# Pinduino-Nano-WPC-adaptor-panalized.net
KiCad netlist of a schematic drawn in EAGLE
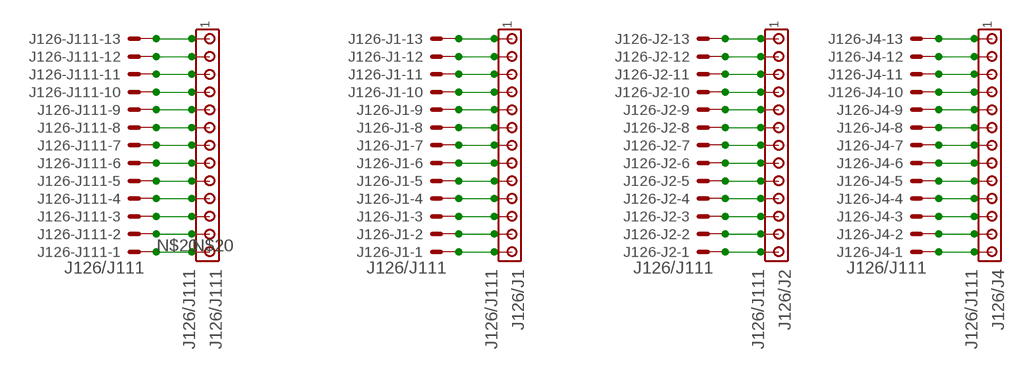
[diagram p0: schematic, sheet 1]

(export (version "E")
  (design (tool "Eeschema 10.0.6"))
  (components
    (comp (ref "J126-J1")
      (value "J126/J111")
      (footprint "eagle-import:KK-156-13")
      (libsource (lib "eagle-import") (part "KK-156-13"))
    )
    (comp (ref "J126-J2")
      (value "J126/J111")
      (footprint "eagle-import:KK-156-13")
      (libsource (lib "eagle-import") (part "KK-156-13"))
    )
    (comp (ref "J126-J4")
      (value "J126/J111")
      (footprint "eagle-import:KK-156-13")
      (libsource (lib "eagle-import") (part "KK-156-13"))
    )
    (comp (ref "J126-J111")
      (value "J126/J111")
      (footprint "eagle-import:KK-156-13")
      (libsource (lib "eagle-import") (part "KK-156-13"))
    )
    (comp (ref "J126/J1")
      (value "J126/J111")
      (footprint "eagle-import:1X13MTA")
      (libsource (lib "eagle-import") (part "MTA13-156"))
    )
    (comp (ref "J126/J2")
      (value "J126/J111")
      (footprint "eagle-import:1X13MTA")
      (libsource (lib "eagle-import") (part "MTA13-156"))
    )
    (comp (ref "J126/J4")
      (value "J126/J111")
      (footprint "eagle-import:1X13MTA")
      (libsource (lib "eagle-import") (part "MTA13-156"))
    )
    (comp (ref "J126/J111")
      (value "J126/J111")
      (footprint "eagle-import:1X13MTA")
      (libsource (lib "eagle-import") (part "MTA13-156"))
    )
  )
  (nets
    (net (code "1") (name "/N$20") (class "Default")
      (node (ref "J126-J111") (pin "2") (pinfunction "S_2") (pintype "passive"))
      (node (ref "J126/J111") (pin "12") (pinfunction "12_12") (pintype "passive"))
    )
    (net (code "2") (name "Net-(J126-J1A-S)") (class "Default")
      (node (ref "J126-J1") (pin "1") (pinfunction "S_1") (pintype "passive"))
      (node (ref "J126/J1") (pin "13") (pinfunction "13_13") (pintype "passive"))
    )
    (net (code "3") (name "Net-(J126-J1B-S)") (class "Default")
      (node (ref "J126-J1") (pin "10") (pinfunction "S_10") (pintype "passive"))
      (node (ref "J126/J1") (pin "4") (pinfunction "4_4") (pintype "passive"))
    )
    (net (code "4") (name "Net-(J126-J1C-S)") (class "Default")
      (node (ref "J126-J1") (pin "11") (pinfunction "S_11") (pintype "passive"))
      (node (ref "J126/J1") (pin "3") (pinfunction "3_3") (pintype "passive"))
    )
    (net (code "5") (name "Net-(J126-J1D-S)") (class "Default")
      (node (ref "J126-J1") (pin "12") (pinfunction "S_12") (pintype "passive"))
      (node (ref "J126/J1") (pin "2") (pinfunction "2_2") (pintype "passive"))
    )
    (net (code "6") (name "Net-(J126-J1E-S)") (class "Default")
      (node (ref "J126-J1") (pin "13") (pinfunction "S_13") (pintype "passive"))
      (node (ref "J126/J1") (pin "1") (pinfunction "1_1") (pintype "passive"))
    )
    (net (code "7") (name "Net-(J126-J1F-S)") (class "Default")
      (node (ref "J126-J1") (pin "2") (pinfunction "S_2") (pintype "passive"))
      (node (ref "J126/J1") (pin "12") (pinfunction "12_12") (pintype "passive"))
    )
    (net (code "8") (name "Net-(J126-J1G-S)") (class "Default")
      (node (ref "J126-J1") (pin "3") (pinfunction "S_3") (pintype "passive"))
      (node (ref "J126/J1") (pin "11") (pinfunction "11_11") (pintype "passive"))
    )
    (net (code "9") (name "Net-(J126-J1H-S)") (class "Default")
      (node (ref "J126-J1") (pin "4") (pinfunction "S_4") (pintype "passive"))
      (node (ref "J126/J1") (pin "10") (pinfunction "10_10") (pintype "passive"))
    )
    (net (code "10") (name "Net-(J126-J1I-S)") (class "Default")
      (node (ref "J126-J1") (pin "5") (pinfunction "S_5") (pintype "passive"))
      (node (ref "J126/J1") (pin "9") (pinfunction "9_9") (pintype "passive"))
    )
    (net (code "11") (name "Net-(J126-J1J-S)") (class "Default")
      (node (ref "J126-J1") (pin "6") (pinfunction "S_6") (pintype "passive"))
      (node (ref "J126/J1") (pin "8") (pinfunction "8_8") (pintype "passive"))
    )
    (net (code "12") (name "Net-(J126-J1K-S)") (class "Default")
      (node (ref "J126-J1") (pin "7") (pinfunction "S_7") (pintype "passive"))
      (node (ref "J126/J1") (pin "7") (pinfunction "7_7") (pintype "passive"))
    )
    (net (code "13") (name "Net-(J126-J1L-S)") (class "Default")
      (node (ref "J126-J1") (pin "8") (pinfunction "S_8") (pintype "passive"))
      (node (ref "J126/J1") (pin "6") (pinfunction "6_6") (pintype "passive"))
    )
    (net (code "14") (name "Net-(J126-J1M-S)") (class "Default")
      (node (ref "J126-J1") (pin "9") (pinfunction "S_9") (pintype "passive"))
      (node (ref "J126/J1") (pin "5") (pinfunction "5_5") (pintype "passive"))
    )
    (net (code "15") (name "Net-(J126-J2A-S)") (class "Default")
      (node (ref "J126-J2") (pin "1") (pinfunction "S_1") (pintype "passive"))
      (node (ref "J126/J2") (pin "13") (pinfunction "13_13") (pintype "passive"))
    )
    (net (code "16") (name "Net-(J126-J2B-S)") (class "Default")
      (node (ref "J126-J2") (pin "10") (pinfunction "S_10") (pintype "passive"))
      (node (ref "J126/J2") (pin "4") (pinfunction "4_4") (pintype "passive"))
    )
    (net (code "17") (name "Net-(J126-J2C-S)") (class "Default")
      (node (ref "J126-J2") (pin "11") (pinfunction "S_11") (pintype "passive"))
      (node (ref "J126/J2") (pin "3") (pinfunction "3_3") (pintype "passive"))
    )
    (net (code "18") (name "Net-(J126-J2D-S)") (class "Default")
      (node (ref "J126-J2") (pin "12") (pinfunction "S_12") (pintype "passive"))
      (node (ref "J126/J2") (pin "2") (pinfunction "2_2") (pintype "passive"))
    )
    (net (code "19") (name "Net-(J126-J2E-S)") (class "Default")
      (node (ref "J126-J2") (pin "13") (pinfunction "S_13") (pintype "passive"))
      (node (ref "J126/J2") (pin "1") (pinfunction "1_1") (pintype "passive"))
    )
    (net (code "20") (name "Net-(J126-J2F-S)") (class "Default")
      (node (ref "J126-J2") (pin "2") (pinfunction "S_2") (pintype "passive"))
      (node (ref "J126/J2") (pin "12") (pinfunction "12_12") (pintype "passive"))
    )
    (net (code "21") (name "Net-(J126-J2G-S)") (class "Default")
      (node (ref "J126-J2") (pin "3") (pinfunction "S_3") (pintype "passive"))
      (node (ref "J126/J2") (pin "11") (pinfunction "11_11") (pintype "passive"))
    )
    (net (code "22") (name "Net-(J126-J2H-S)") (class "Default")
      (node (ref "J126-J2") (pin "4") (pinfunction "S_4") (pintype "passive"))
      (node (ref "J126/J2") (pin "10") (pinfunction "10_10") (pintype "passive"))
    )
    (net (code "23") (name "Net-(J126-J2I-S)") (class "Default")
      (node (ref "J126-J2") (pin "5") (pinfunction "S_5") (pintype "passive"))
      (node (ref "J126/J2") (pin "9") (pinfunction "9_9") (pintype "passive"))
    )
    (net (code "24") (name "Net-(J126-J2J-S)") (class "Default")
      (node (ref "J126-J2") (pin "6") (pinfunction "S_6") (pintype "passive"))
      (node (ref "J126/J2") (pin "8") (pinfunction "8_8") (pintype "passive"))
    )
    (net (code "25") (name "Net-(J126-J2K-S)") (class "Default")
      (node (ref "J126-J2") (pin "7") (pinfunction "S_7") (pintype "passive"))
      (node (ref "J126/J2") (pin "7") (pinfunction "7_7") (pintype "passive"))
    )
    (net (code "26") (name "Net-(J126-J2L-S)") (class "Default")
      (node (ref "J126-J2") (pin "8") (pinfunction "S_8") (pintype "passive"))
      (node (ref "J126/J2") (pin "6") (pinfunction "6_6") (pintype "passive"))
    )
    (net (code "27") (name "Net-(J126-J2M-S)") (class "Default")
      (node (ref "J126-J2") (pin "9") (pinfunction "S_9") (pintype "passive"))
      (node (ref "J126/J2") (pin "5") (pinfunction "5_5") (pintype "passive"))
    )
    (net (code "28") (name "Net-(J126-J4A-S)") (class "Default")
      (node (ref "J126-J4") (pin "1") (pinfunction "S_1") (pintype "passive"))
      (node (ref "J126/J4") (pin "13") (pinfunction "13_13") (pintype "passive"))
    )
    (net (code "29") (name "Net-(J126-J4B-S)") (class "Default")
      (node (ref "J126-J4") (pin "10") (pinfunction "S_10") (pintype "passive"))
      (node (ref "J126/J4") (pin "4") (pinfunction "4_4") (pintype "passive"))
    )
    (net (code "30") (name "Net-(J126-J4C-S)") (class "Default")
      (node (ref "J126-J4") (pin "11") (pinfunction "S_11") (pintype "passive"))
      (node (ref "J126/J4") (pin "3") (pinfunction "3_3") (pintype "passive"))
    )
    (net (code "31") (name "Net-(J126-J4D-S)") (class "Default")
      (node (ref "J126-J4") (pin "12") (pinfunction "S_12") (pintype "passive"))
      (node (ref "J126/J4") (pin "2") (pinfunction "2_2") (pintype "passive"))
    )
    (net (code "32") (name "Net-(J126-J4E-S)") (class "Default")
      (node (ref "J126-J4") (pin "13") (pinfunction "S_13") (pintype "passive"))
      (node (ref "J126/J4") (pin "1") (pinfunction "1_1") (pintype "passive"))
    )
    (net (code "33") (name "Net-(J126-J4F-S)") (class "Default")
      (node (ref "J126-J4") (pin "2") (pinfunction "S_2") (pintype "passive"))
      (node (ref "J126/J4") (pin "12") (pinfunction "12_12") (pintype "passive"))
    )
    (net (code "34") (name "Net-(J126-J4G-S)") (class "Default")
      (node (ref "J126-J4") (pin "3") (pinfunction "S_3") (pintype "passive"))
      (node (ref "J126/J4") (pin "11") (pinfunction "11_11") (pintype "passive"))
    )
    (net (code "35") (name "Net-(J126-J4H-S)") (class "Default")
      (node (ref "J126-J4") (pin "4") (pinfunction "S_4") (pintype "passive"))
      (node (ref "J126/J4") (pin "10") (pinfunction "10_10") (pintype "passive"))
    )
    (net (code "36") (name "Net-(J126-J4I-S)") (class "Default")
      (node (ref "J126-J4") (pin "5") (pinfunction "S_5") (pintype "passive"))
      (node (ref "J126/J4") (pin "9") (pinfunction "9_9") (pintype "passive"))
    )
    (net (code "37") (name "Net-(J126-J4J-S)") (class "Default")
      (node (ref "J126-J4") (pin "6") (pinfunction "S_6") (pintype "passive"))
      (node (ref "J126/J4") (pin "8") (pinfunction "8_8") (pintype "passive"))
    )
    (net (code "38") (name "Net-(J126-J4K-S)") (class "Default")
      (node (ref "J126-J4") (pin "7") (pinfunction "S_7") (pintype "passive"))
      (node (ref "J126/J4") (pin "7") (pinfunction "7_7") (pintype "passive"))
    )
    (net (code "39") (name "Net-(J126-J4L-S)") (class "Default")
      (node (ref "J126-J4") (pin "8") (pinfunction "S_8") (pintype "passive"))
      (node (ref "J126/J4") (pin "6") (pinfunction "6_6") (pintype "passive"))
    )
    (net (code "40") (name "Net-(J126-J4M-S)") (class "Default")
      (node (ref "J126-J4") (pin "9") (pinfunction "S_9") (pintype "passive"))
      (node (ref "J126/J4") (pin "5") (pinfunction "5_5") (pintype "passive"))
    )
    (net (code "41") (name "Net-(J126-J111A-S)") (class "Default")
      (node (ref "J126-J111") (pin "1") (pinfunction "S_1") (pintype "passive"))
      (node (ref "J126/J111") (pin "13") (pinfunction "13_13") (pintype "passive"))
    )
    (net (code "42") (name "Net-(J126-J111B-S)") (class "Default")
      (node (ref "J126-J111") (pin "10") (pinfunction "S_10") (pintype "passive"))
      (node (ref "J126/J111") (pin "4") (pinfunction "4_4") (pintype "passive"))
    )
    (net (code "43") (name "Net-(J126-J111C-S)") (class "Default")
      (node (ref "J126-J111") (pin "11") (pinfunction "S_11") (pintype "passive"))
      (node (ref "J126/J111") (pin "3") (pinfunction "3_3") (pintype "passive"))
    )
    (net (code "44") (name "Net-(J126-J111D-S)") (class "Default")
      (node (ref "J126-J111") (pin "12") (pinfunction "S_12") (pintype "passive"))
      (node (ref "J126/J111") (pin "2") (pinfunction "2_2") (pintype "passive"))
    )
    (net (code "45") (name "Net-(J126-J111E-S)") (class "Default")
      (node (ref "J126-J111") (pin "13") (pinfunction "S_13") (pintype "passive"))
      (node (ref "J126/J111") (pin "1") (pinfunction "1_1") (pintype "passive"))
    )
    (net (code "46") (name "Net-(J126-J111G-S)") (class "Default")
      (node (ref "J126-J111") (pin "3") (pinfunction "S_3") (pintype "passive"))
      (node (ref "J126/J111") (pin "11") (pinfunction "11_11") (pintype "passive"))
    )
    (net (code "47") (name "Net-(J126-J111H-S)") (class "Default")
      (node (ref "J126-J111") (pin "4") (pinfunction "S_4") (pintype "passive"))
      (node (ref "J126/J111") (pin "10") (pinfunction "10_10") (pintype "passive"))
    )
    (net (code "48") (name "Net-(J126-J111I-S)") (class "Default")
      (node (ref "J126-J111") (pin "5") (pinfunction "S_5") (pintype "passive"))
      (node (ref "J126/J111") (pin "9") (pinfunction "9_9") (pintype "passive"))
    )
    (net (code "49") (name "Net-(J126-J111J-S)") (class "Default")
      (node (ref "J126-J111") (pin "6") (pinfunction "S_6") (pintype "passive"))
      (node (ref "J126/J111") (pin "8") (pinfunction "8_8") (pintype "passive"))
    )
    (net (code "50") (name "Net-(J126-J111K-S)") (class "Default")
      (node (ref "J126-J111") (pin "7") (pinfunction "S_7") (pintype "passive"))
      (node (ref "J126/J111") (pin "7") (pinfunction "7_7") (pintype "passive"))
    )
    (net (code "51") (name "Net-(J126-J111L-S)") (class "Default")
      (node (ref "J126-J111") (pin "8") (pinfunction "S_8") (pintype "passive"))
      (node (ref "J126/J111") (pin "6") (pinfunction "6_6") (pintype "passive"))
    )
    (net (code "52") (name "Net-(J126-J111M-S)") (class "Default")
      (node (ref "J126-J111") (pin "9") (pinfunction "S_9") (pintype "passive"))
      (node (ref "J126/J111") (pin "5") (pinfunction "5_5") (pintype "passive"))
    )
  )
)
